# pcb_eda.net
KiCad netlist of a schematic drawn in EasyEDA Pro
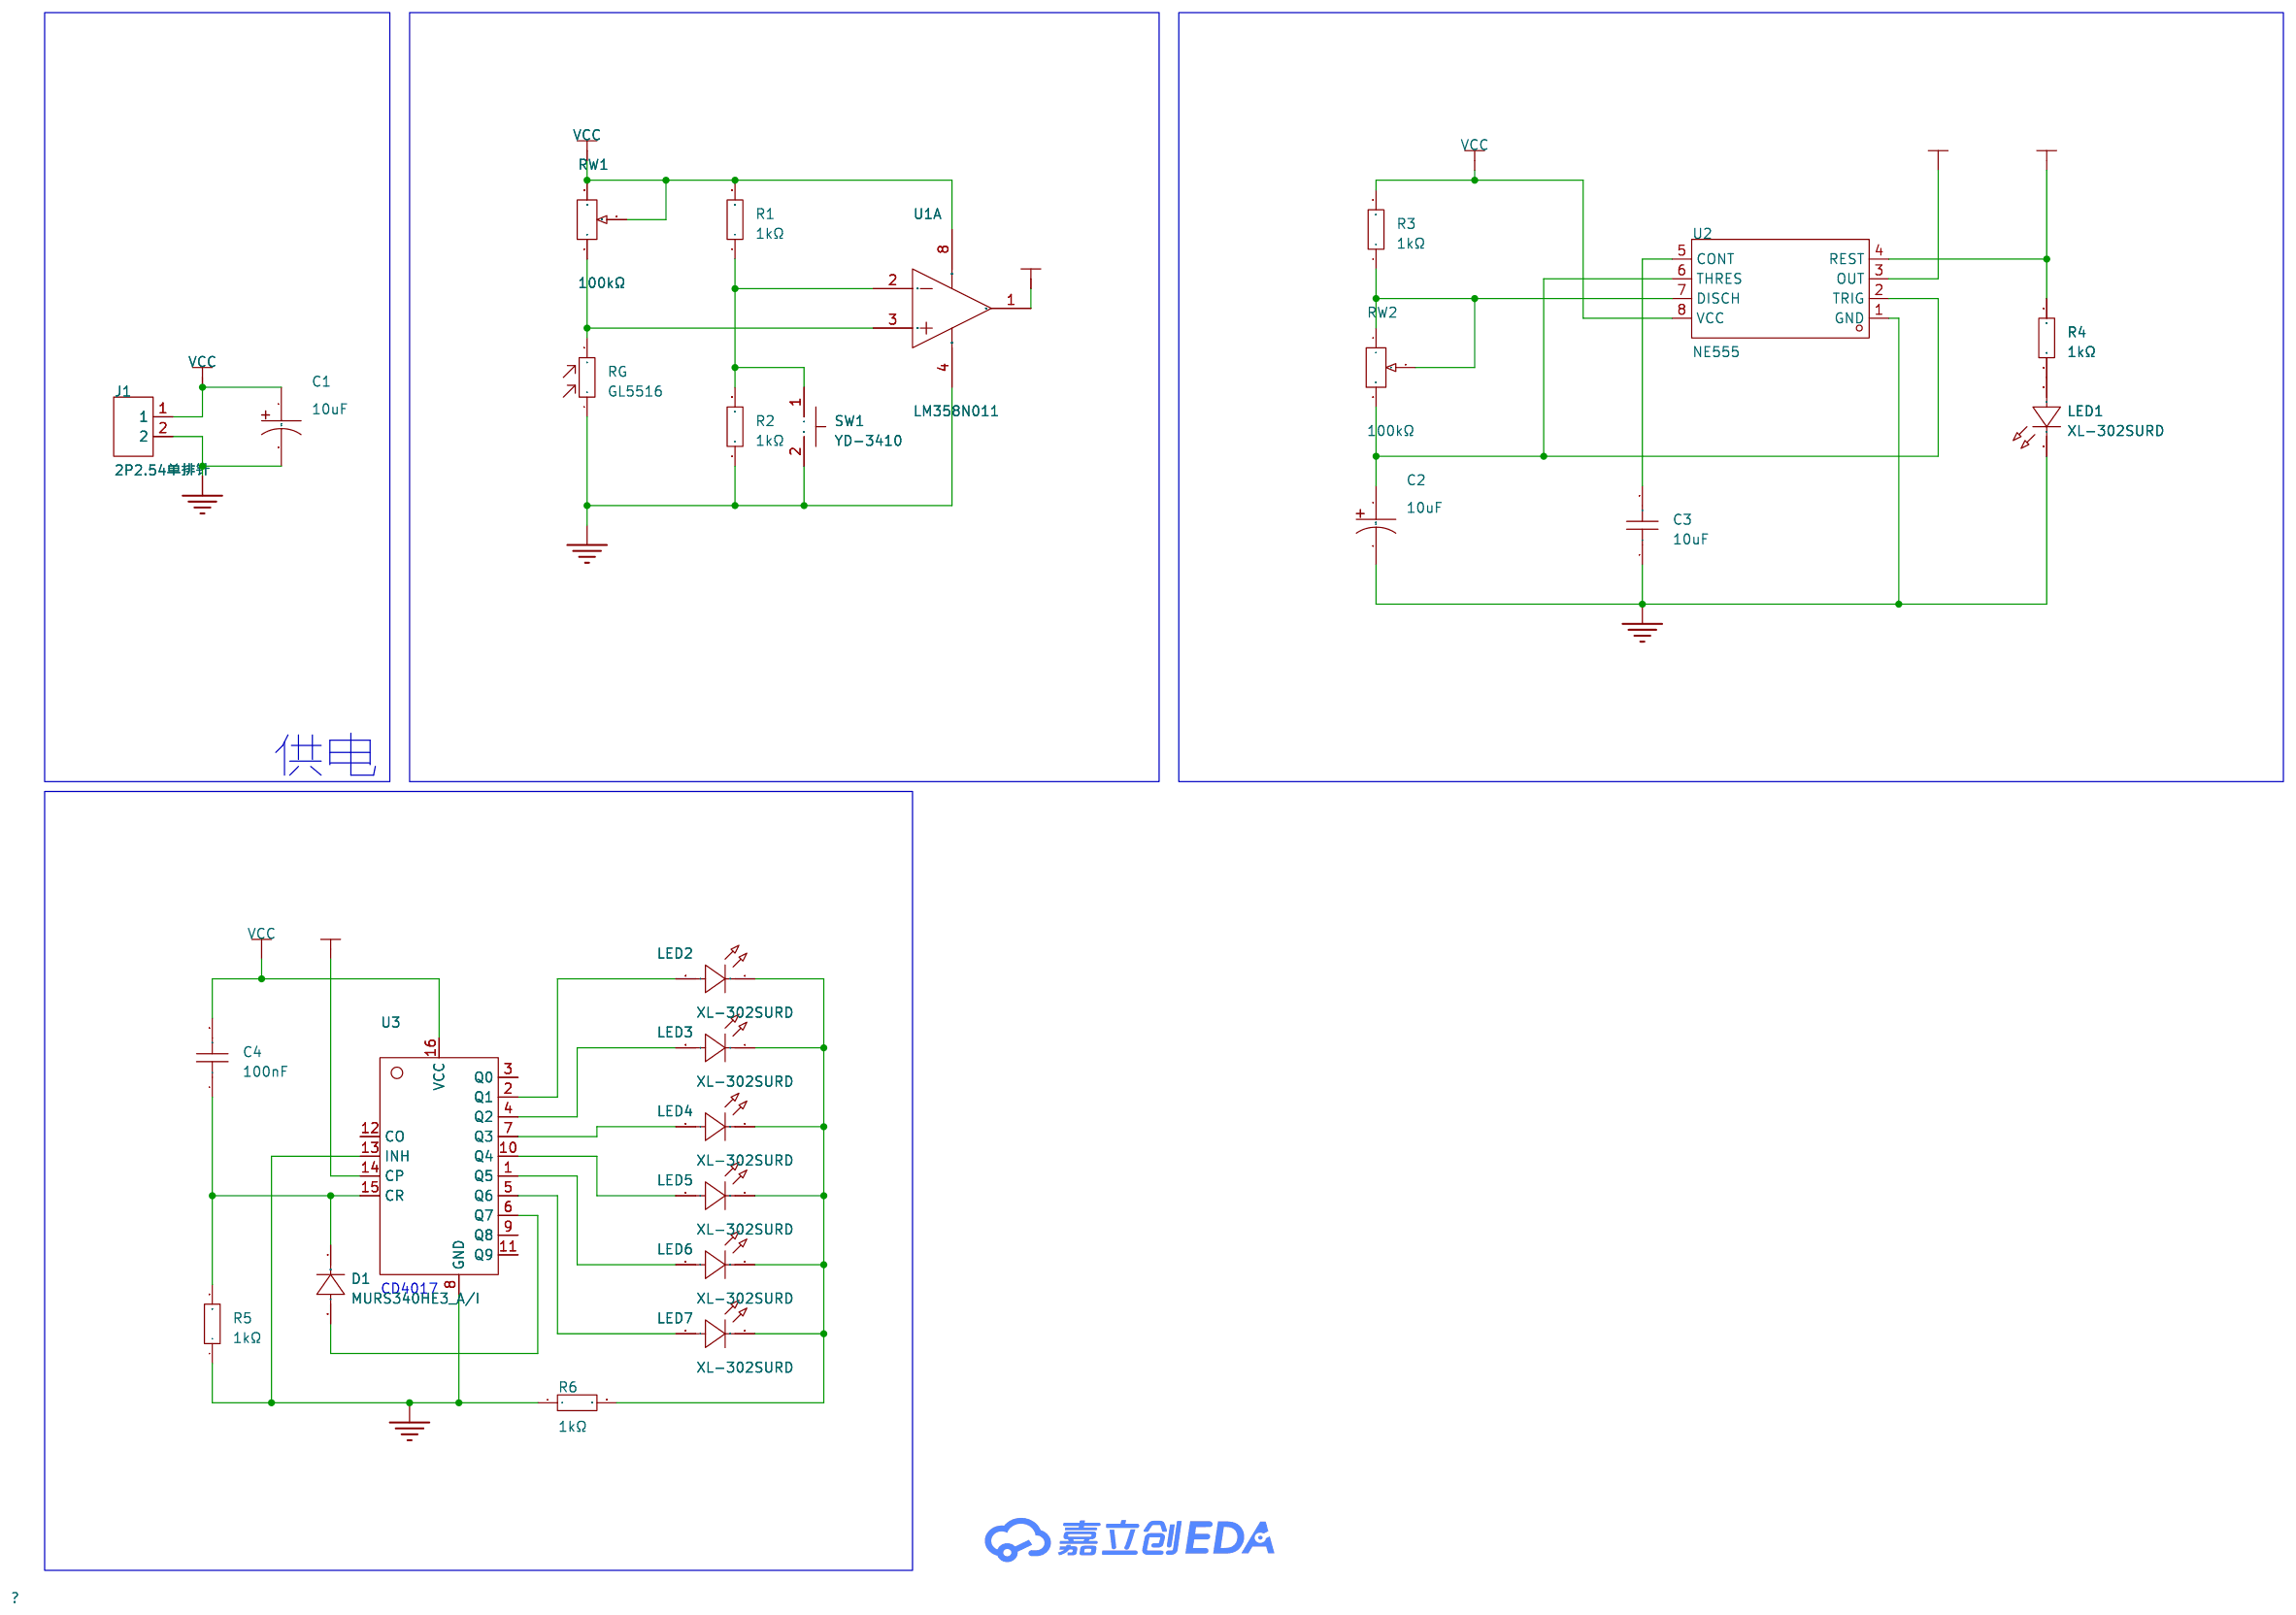
[diagram p0: schematic sheet]

(export (version "E")
  (design (tool "Eeschema 10.0.6"))
  (components
    (comp (ref "C1")
      (value "10uF")
      (footprint "easyedapro:CAP-TH_BD8.0-P5.00-D1.0-FD")
      (description "容值:10uF;精度:±20%;额定电压:160V;纹波电流:82mA@120Hz;")
      (fields
        (field (name "Manufacturer Part") "MHA160V10M8*11.5 5.0TP")
        (field (name "Manufacturer") "SAMYOUNG(韩国三莹)")
      )
      (libsource (lib "easyedapro") (part "MHA160VB10M8*11.5_5.0TP"))
    )
    (comp (ref "C2")
      (value "10uF")
      (footprint "easyedapro:CAP-TH_BD8.0-P5.00-D1.0-FD")
      (description "容值:10uF;精度:±20%;额定电压:160V;纹波电流:82mA@120Hz;")
      (fields
        (field (name "Manufacturer Part") "MHA160V10M8*11.5 5.0TP")
        (field (name "Manufacturer") "SAMYOUNG(韩国三莹)")
      )
      (libsource (lib "easyedapro") (part "MHA160VB10M8*11.5_5.0TP"))
    )
    (comp (ref "C3")
      (value "10uF")
      (footprint "easyedapro:CAP-TH_L8.5-W5.0-P5.00-D1.2")
      (description "容值:100nF;精度:±10%;额定电压:50V;温度系数:X7R;")
      (fields
        (field (name "Manufacturer Part") "CGA0603X5R106K100JT")
        (field (name "Manufacturer") "HRE(芯声)")
      )
      (libsource (lib "easyedapro") (part "CT4-0805B104K500F3"))
    )
    (comp (ref "C4")
      (value "100nF")
      (footprint "easyedapro:CAP-TH_L8.5-W5.0-P5.00-D1.2")
      (description "容值:100nF;精度:±10%;额定电压:50V;温度系数:X7R;")
      (fields
        (field (name "Manufacturer Part") "CGA0603X7R104K500JT")
        (field (name "Manufacturer") "HRE(芯声)")
      )
      (libsource (lib "easyedapro") (part "CT4-0805B104K500F3"))
    )
    (comp (ref "D1")
      (value "MURS340HE3_A/I")
      (footprint "easyedapro:SMC_L6.9-W5.9-LS7.9-RD")
      (description "二极管配置:1个独立式;正向压降(Vf):1.25V;直流反向耐压(Vr):400V;整流电流:3A;反向恢复时间(Trr):50ns;")
      (fields (field (name "Manufacturer") "VISHAY(威世)"))
      (libsource (lib "easyedapro") (part "MURS340HE3_A/I"))
    )
    (comp (ref "J1")
      (value "2P2.54单排针")
      (footprint "easyedapro:HDR-TH_2P-P2.54-V-M")
      (libsource (lib "easyedapro") (part "2P2.54单排针"))
    )
    (comp (ref "LED1")
      (value "XL-302SURD")
      (footprint "easyedapro:LED-TH_BD3.8-P2.54-RD")
      (fields (field (name "Manufacturer") "XINGLIGHT(成兴光)"))
      (libsource (lib "easyedapro") (part "XL-302SURD"))
    )
    (comp (ref "LED2")
      (value "XL-302SURD")
      (footprint "easyedapro:LED-TH_BD3.8-P2.54-RD")
      (fields (field (name "Manufacturer") "XINGLIGHT(成兴光)"))
      (libsource (lib "easyedapro") (part "XL-302SURD"))
    )
    (comp (ref "LED3")
      (value "XL-302SURD")
      (footprint "easyedapro:LED-TH_BD3.8-P2.54-RD")
      (fields (field (name "Manufacturer") "XINGLIGHT(成兴光)"))
      (libsource (lib "easyedapro") (part "XL-302SURD"))
    )
    (comp (ref "LED4")
      (value "XL-302SURD")
      (footprint "easyedapro:LED-TH_BD3.8-P2.54-RD")
      (fields (field (name "Manufacturer") "XINGLIGHT(成兴光)"))
      (libsource (lib "easyedapro") (part "XL-302SURD"))
    )
    (comp (ref "LED5")
      (value "XL-302SURD")
      (footprint "easyedapro:LED-TH_BD3.8-P2.54-RD")
      (fields (field (name "Manufacturer") "XINGLIGHT(成兴光)"))
      (libsource (lib "easyedapro") (part "XL-302SURD"))
    )
    (comp (ref "LED6")
      (value "XL-302SURD")
      (footprint "easyedapro:LED-TH_BD3.8-P2.54-RD")
      (fields (field (name "Manufacturer") "XINGLIGHT(成兴光)"))
      (libsource (lib "easyedapro") (part "XL-302SURD"))
    )
    (comp (ref "LED7")
      (value "XL-302SURD")
      (footprint "easyedapro:LED-TH_BD3.8-P2.54-RD")
      (fields (field (name "Manufacturer") "XINGLIGHT(成兴光)"))
      (libsource (lib "easyedapro") (part "XL-302SURD"))
    )
    (comp (ref "R1")
      (value "1kΩ")
      (footprint "easyedapro:R0603")
      (fields
        (field (name "Manufacturer Part") "MFR0W4F1001A50")
        (field (name "Manufacturer") "UNI-ROYAL(厚声)")
      )
      (libsource (lib "easyedapro") (part "电阻"))
    )
    (comp (ref "R2")
      (value "1kΩ")
      (footprint "easyedapro:R0603")
      (fields
        (field (name "Manufacturer Part") "MFR0W4F1001A50")
        (field (name "Manufacturer") "UNI-ROYAL(厚声)")
      )
      (libsource (lib "easyedapro") (part "电阻"))
    )
    (comp (ref "R3")
      (value "1kΩ")
      (footprint "easyedapro:R0603")
      (fields
        (field (name "Manufacturer Part") "MFR0W4F1001A50")
        (field (name "Manufacturer") "UNI-ROYAL(厚声)")
      )
      (libsource (lib "easyedapro") (part "电阻"))
    )
    (comp (ref "R4")
      (value "1kΩ")
      (footprint "easyedapro:R0603")
      (fields
        (field (name "Manufacturer Part") "MFR0W4F1001A50")
        (field (name "Manufacturer") "UNI-ROYAL(厚声)")
      )
      (libsource (lib "easyedapro") (part "电阻"))
    )
    (comp (ref "R5")
      (value "1kΩ")
      (footprint "easyedapro:R0603")
      (fields
        (field (name "Manufacturer Part") "MFR0W4F1001A50")
        (field (name "Manufacturer") "UNI-ROYAL(厚声)")
      )
      (libsource (lib "easyedapro") (part "电阻"))
    )
    (comp (ref "R6")
      (value "1kΩ")
      (footprint "easyedapro:R0603")
      (fields
        (field (name "Manufacturer Part") "MFR0W4F1001A50")
        (field (name "Manufacturer") "UNI-ROYAL(厚声)")
      )
      (libsource (lib "easyedapro") (part "电阻"))
    )
    (comp (ref "RG")
      (value "GL5516")
      (footprint "easyedapro:RES-TH_L5.1-W4.3-P3.40-D0.5")
      (description "暗电阻:500kΩ;亮电阻 @ 10Lux:5kΩ~10kΩ;光谱峰值(波长):540nm;")
      (fields (field (name "Manufacturer") "森霸"))
      (libsource (lib "easyedapro") (part "GL5516"))
    )
    (comp (ref "RW1")
      (value "100kΩ")
      (footprint "easyedapro:RES-ADJ-TH_3296W-1-203")
      (description "阻值:100kΩ;精度:±10%;功率:500mW;温度系数:±250ppm/°C;")
      (fields (field (name "Manufacturer Part") "3296W-1-104") (field (name "Manufacturer") "JIERR(捷而瑞)"))
      (libsource (lib "easyedapro") (part "3296W-1-104_C48997936"))
    )
    (comp (ref "RW2")
      (value "100kΩ")
      (footprint "easyedapro:RES-ADJ-TH_3296W-1-203")
      (description "阻值:100kΩ;精度:±10%;功率:500mW;温度系数:±250ppm/°C;")
      (fields (field (name "Manufacturer Part") "3296W-1-104") (field (name "Manufacturer") "JIERR(捷而瑞)"))
      (libsource (lib "easyedapro") (part "3296W-1-104_C48997936"))
    )
    (comp (ref "SW1")
      (value "YD-3410")
      (footprint "easyedapro:SW-SMD_L3.9-W2.9-LS4.8-EH-A")
      (libsource (lib "easyedapro") (part "YD-3410"))
    )
    (comp (ref "U1")
      (value "LM358N011")
      (footprint "easyedapro:PDIP-8_L9.6-W6.4-P2.54-LS7.6-BL")
      (fields (field (name "Manufacturer") "GMIC(绿微)"))
      (libsource (lib "easyedapro") (part "LM358N011"))
    )
    (comp (ref "U2")
      (value "NE555")
      (footprint "easyedapro:DIP-8_L9.7-W6.4-P2.54-LS7.6-BL")
      (libsource (lib "easyedapro") (part "NE555_C504550"))
    )
    (comp (ref "U3")
      (value "~")
      (footprint "easyedapro:DIP-16")
      (libsource (lib "easyedapro") (part "CD4017_course"))
    )
  )
  (nets
    (net (code "1") (name "GND") (class "Default")
      (node (ref "C1") (pin "2") (pinfunction "2_2") (pintype "unspecified"))
      (node (ref "C2") (pin "2") (pinfunction "2_2") (pintype "unspecified"))
      (node (ref "C3") (pin "1") (pinfunction "1_1") (pintype "unspecified"))
      (node (ref "J1") (pin "2") (pinfunction "2_2") (pintype "unspecified"))
      (node (ref "LED1") (pin "1") (pinfunction "K_1") (pintype "unspecified"))
      (node (ref "R2") (pin "1") (pinfunction "1_1") (pintype "input"))
      (node (ref "R5") (pin "1") (pinfunction "1_1") (pintype "input"))
      (node (ref "R6") (pin "1") (pinfunction "1_1") (pintype "input"))
      (node (ref "RG") (pin "1") (pinfunction "1_1") (pintype "input"))
      (node (ref "SW1") (pin "2") (pinfunction "2_2") (pintype "unspecified"))
      (node (ref "U1") (pin "4") (pinfunction "GND_4") (pintype "unspecified"))
      (node (ref "U2") (pin "1") (pinfunction "GND_1") (pintype "unspecified"))
      (node (ref "U3") (pin "13") (pinfunction "INH_13") (pintype "input"))
      (node (ref "U3") (pin "8") (pinfunction "GND_8") (pintype "input"))
    )
    (net (code "2") (name "Net-(D1-A)") (class "Default")
      (node (ref "D1") (pin "2") (pinfunction "A_2") (pintype "unspecified"))
      (node (ref "U3") (pin "6") (pinfunction "Q7_6") (pintype "input"))
    )
    (net (code "3") (name "Net-(D1-C)") (class "Default")
      (node (ref "C4") (pin "1") (pinfunction "1_1") (pintype "unspecified"))
      (node (ref "D1") (pin "1") (pinfunction "C_1") (pintype "unspecified"))
      (node (ref "R5") (pin "2") (pinfunction "2_2") (pintype "input"))
      (node (ref "U3") (pin "15") (pinfunction "CR_15") (pintype "input"))
    )
    (net (code "4") (name "Net-(LED1-A)") (class "Default")
      (node (ref "LED1") (pin "2") (pinfunction "A_2") (pintype "unspecified"))
      (node (ref "R4") (pin "2") (pinfunction "2_2") (pintype "input"))
    )
    (net (code "5") (name "Net-(LED2-A)") (class "Default")
      (node (ref "LED2") (pin "2") (pinfunction "A_2") (pintype "unspecified"))
      (node (ref "U3") (pin "2") (pinfunction "Q1_2") (pintype "input"))
    )
    (net (code "6") (name "Net-(LED2-K)") (class "Default")
      (node (ref "LED2") (pin "1") (pinfunction "K_1") (pintype "unspecified"))
      (node (ref "LED3") (pin "1") (pinfunction "K_1") (pintype "unspecified"))
      (node (ref "LED4") (pin "1") (pinfunction "K_1") (pintype "unspecified"))
      (node (ref "LED5") (pin "1") (pinfunction "K_1") (pintype "unspecified"))
      (node (ref "LED6") (pin "1") (pinfunction "K_1") (pintype "unspecified"))
      (node (ref "LED7") (pin "1") (pinfunction "K_1") (pintype "unspecified"))
      (node (ref "R6") (pin "2") (pinfunction "2_2") (pintype "input"))
    )
    (net (code "7") (name "Net-(LED3-A)") (class "Default")
      (node (ref "LED3") (pin "2") (pinfunction "A_2") (pintype "unspecified"))
      (node (ref "U3") (pin "4") (pinfunction "Q2_4") (pintype "input"))
    )
    (net (code "8") (name "Net-(LED4-A)") (class "Default")
      (node (ref "LED4") (pin "2") (pinfunction "A_2") (pintype "unspecified"))
      (node (ref "U3") (pin "7") (pinfunction "Q3_7") (pintype "input"))
    )
    (net (code "9") (name "Net-(LED5-A)") (class "Default")
      (node (ref "LED5") (pin "2") (pinfunction "A_2") (pintype "unspecified"))
      (node (ref "U3") (pin "10") (pinfunction "Q4_10") (pintype "input"))
    )
    (net (code "10") (name "Net-(LED6-A)") (class "Default")
      (node (ref "LED6") (pin "2") (pinfunction "A_2") (pintype "unspecified"))
      (node (ref "U3") (pin "1") (pinfunction "Q5_1") (pintype "input"))
    )
    (net (code "11") (name "Net-(LED7-A)") (class "Default")
      (node (ref "LED7") (pin "2") (pinfunction "A_2") (pintype "unspecified"))
      (node (ref "U3") (pin "5") (pinfunction "Q6_5") (pintype "input"))
    )
    (net (code "12") (name "Net-(U1A-IN_A+)") (class "Default")
      (node (ref "RG") (pin "2") (pinfunction "2_2") (pintype "input"))
      (node (ref "RW1") (pin "1") (pinfunction "1_1") (pintype "input"))
      (node (ref "U1") (pin "3") (pinfunction "IN_A+_3") (pintype "unspecified"))
    )
    (net (code "13") (name "Net-(U1A-IN_A-)") (class "Default")
      (node (ref "R1") (pin "1") (pinfunction "1_1") (pintype "input"))
      (node (ref "R2") (pin "2") (pinfunction "2_2") (pintype "input"))
      (node (ref "SW1") (pin "1") (pinfunction "1_1") (pintype "unspecified"))
      (node (ref "U1") (pin "2") (pinfunction "IN_A-_2") (pintype "unspecified"))
    )
    (net (code "14") (name "Net-(U2-CONT)") (class "Default")
      (node (ref "C3") (pin "2") (pinfunction "2_2") (pintype "unspecified"))
      (node (ref "U2") (pin "5") (pinfunction "CONT_5") (pintype "unspecified"))
    )
    (net (code "15") (name "Net-(U2-DISCH)") (class "Default")
      (node (ref "R3") (pin "1") (pinfunction "1_1") (pintype "input"))
      (node (ref "RW2") (pin "1") (pinfunction "1_1") (pintype "input"))
      (node (ref "RW2") (pin "2") (pinfunction "2_2") (pintype "input"))
      (node (ref "U2") (pin "7") (pinfunction "DISCH_7") (pintype "unspecified"))
    )
    (net (code "16") (name "Net-(U2-THRES)") (class "Default")
      (node (ref "C2") (pin "1") (pinfunction "1_1") (pintype "unspecified"))
      (node (ref "RW2") (pin "3") (pinfunction "3_3") (pintype "input"))
      (node (ref "U2") (pin "2") (pinfunction "TRIG_2") (pintype "unspecified"))
      (node (ref "U2") (pin "6") (pinfunction "THRES_6") (pintype "unspecified"))
    )
    (net (code "17") (name "VAD") (class "Default")
      (node (ref "R4") (pin "1") (pinfunction "1_1") (pintype "input"))
      (node (ref "U1") (pin "1") (pinfunction "OUT_A_1") (pintype "output"))
      (node (ref "U2") (pin "4") (pinfunction "REST_4") (pintype "unspecified"))
    )
    (net (code "18") (name "VCC") (class "Default")
      (node (ref "C1") (pin "1") (pinfunction "1_1") (pintype "unspecified"))
      (node (ref "C4") (pin "2") (pinfunction "2_2") (pintype "unspecified"))
      (node (ref "J1") (pin "1") (pinfunction "1_1") (pintype "unspecified"))
      (node (ref "R1") (pin "2") (pinfunction "2_2") (pintype "input"))
      (node (ref "R3") (pin "2") (pinfunction "2_2") (pintype "input"))
      (node (ref "RW1") (pin "2") (pinfunction "2_2") (pintype "input"))
      (node (ref "RW1") (pin "3") (pinfunction "3_3") (pintype "input"))
      (node (ref "U1") (pin "8") (pinfunction "VCC_8") (pintype "unspecified"))
      (node (ref "U2") (pin "8") (pinfunction "VCC_8") (pintype "unspecified"))
      (node (ref "U3") (pin "16") (pinfunction "VCC_16") (pintype "input"))
    )
    (net (code "19") (name "VOUT") (class "Default")
      (node (ref "U2") (pin "3") (pinfunction "OUT_3") (pintype "unspecified"))
      (node (ref "U3") (pin "14") (pinfunction "CP_14") (pintype "input"))
    )
    (net (code "20") (name "unconnected-(U3-CO-Pad12)") (class "Default")
      (node (ref "U3") (pin "12") (pinfunction "CO_12") (pintype "input"))
    )
    (net (code "21") (name "unconnected-(U3-Q0-Pad3)") (class "Default")
      (node (ref "U3") (pin "3") (pinfunction "Q0_3") (pintype "input"))
    )
    (net (code "22") (name "unconnected-(U3-Q8-Pad9)") (class "Default")
      (node (ref "U3") (pin "9") (pinfunction "Q8_9") (pintype "input"))
    )
    (net (code "23") (name "unconnected-(U3-Q9-Pad11)") (class "Default")
      (node (ref "U3") (pin "11") (pinfunction "Q9_11") (pintype "input"))
    )
  )
)
